# Schemat_easy_eda.net
KiCad netlist of a schematic drawn in EasyEDA
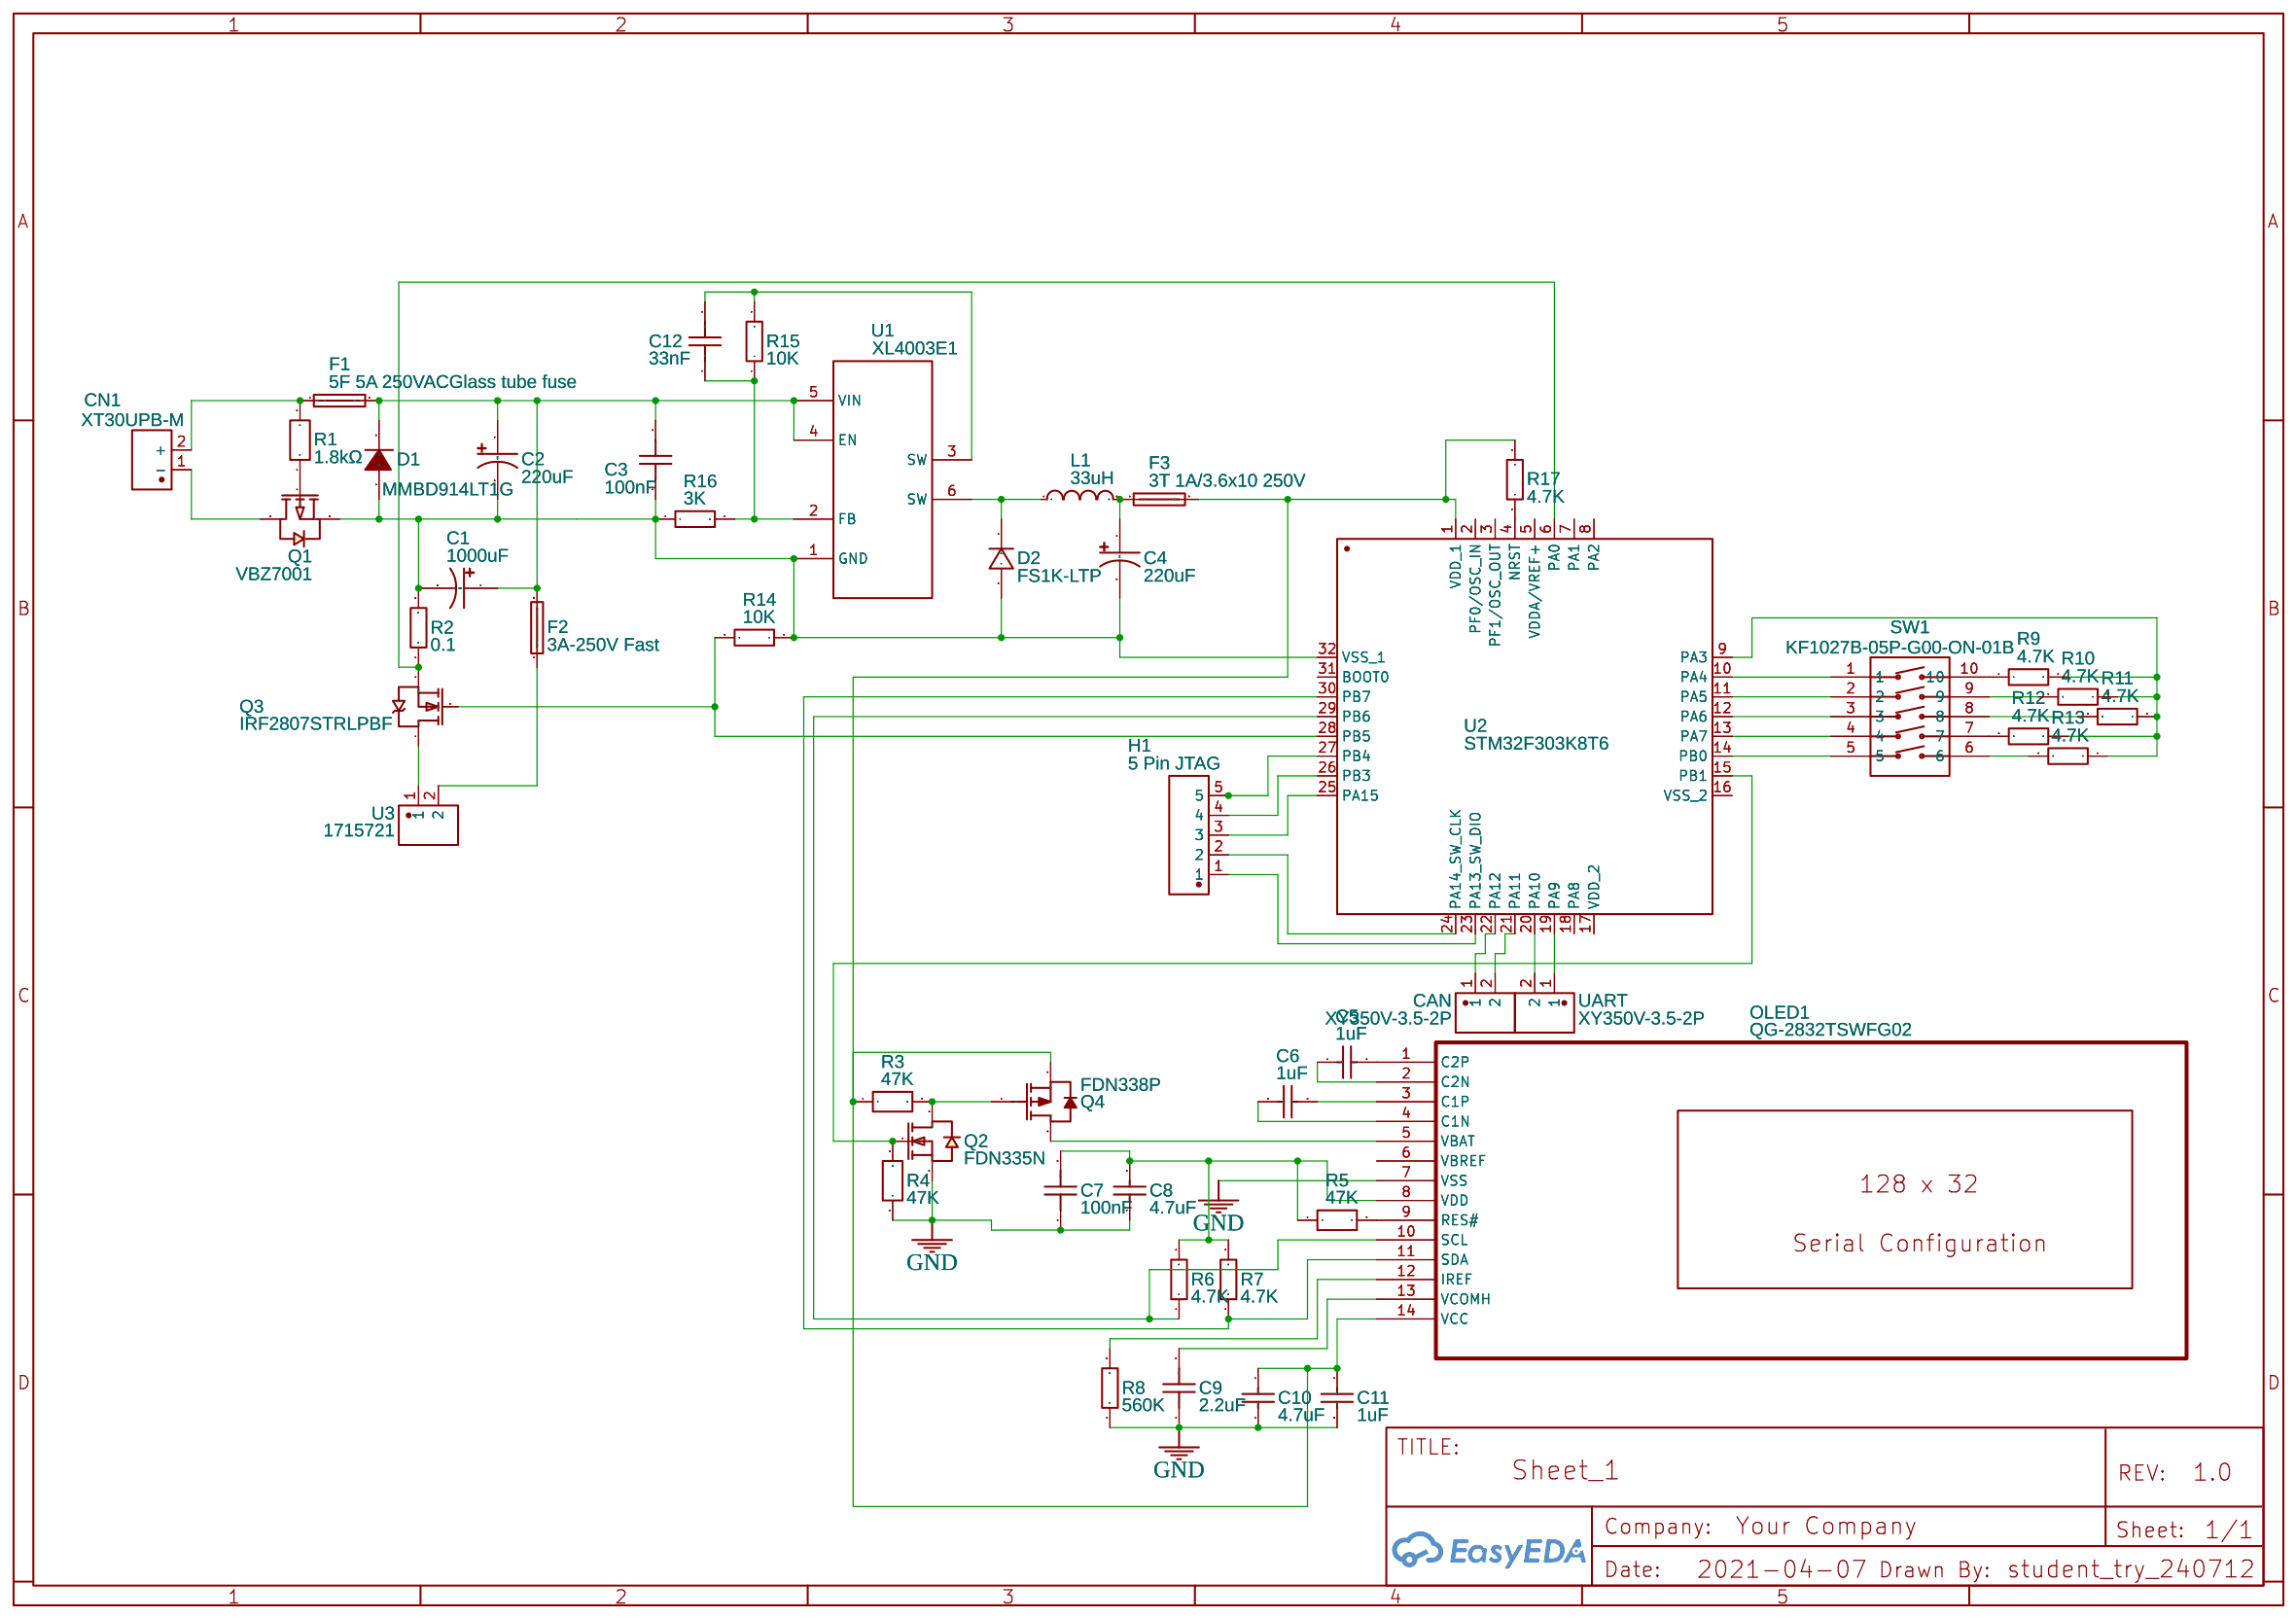
[diagram p0: schematic sheet]

(export (version "E")
  (design (tool "Eeschema 10.0.6"))
  (components
    (comp (ref "C1")
      (value "1000uF")
      (fields
        (field (name "BOM_Manufacturer Part") "LKME2301V102MF")
        (field (name "BOM_Supplier Part") "C442887")
      )
      (libsource (lib "") (part "LKME2301V102MF"))
    )
    (comp (ref "C2")
      (value "220uF")
      (fields
        (field (name "BOM_Manufacturer Part") "RVE1V221M1010")
        (field (name "BOM_Supplier Part") "C88670")
      )
      (libsource (lib "") (part "RVE1V221M1010"))
    )
    (comp (ref "C3")
      (value "100nF")
      (fields
        (field (name "BOM_Manufacturer Part") "CC1H104ZA1FD3F5P10MF")
        (field (name "BOM_Supplier Part") "C254089")
      )
      (libsource (lib "") (part "CC1H104ZA1FD3F5P10MF"))
    )
    (comp (ref "C4")
      (value "220uF")
      (fields
        (field (name "BOM_Manufacturer Part") "VE-221M0JTR-0605")
        (field (name "BOM_Supplier Part") "C134730")
      )
      (libsource (lib "") (part "VE-221M0JTR-0605"))
    )
    (comp (ref "C5")
      (value "1uF")
      (fields
        (field (name "BOM_Manufacturer Part") "CL10B105KA8NNNC")
        (field (name "BOM_Supplier Part") "C29936")
      )
      (libsource (lib "") (part "CL10B105KA8NNNC"))
    )
    (comp (ref "C6")
      (value "1uF")
      (fields
        (field (name "BOM_Manufacturer Part") "CL10B105KA8NNNC")
        (field (name "BOM_Supplier Part") "C29936")
      )
      (libsource (lib "") (part "CL10B105KA8NNNC"))
    )
    (comp (ref "C7")
      (value "100nF")
      (fields
        (field (name "BOM_Manufacturer Part") "GRM155F11C104ZA01D")
        (field (name "BOM_Supplier Part") "C85954")
      )
      (libsource (lib "") (part "GRM155F11C104ZA01D"))
    )
    (comp (ref "C8")
      (value "4.7uF")
      (fields
        (field (name "BOM_Manufacturer Part") "C2012X7R1A475KT000N")
        (field (name "BOM_Supplier Part") "C76639")
      )
      (libsource (lib "") (part "C2012X7R1A475KT000N"))
    )
    (comp (ref "C9")
      (value "2.2uF")
      (fields
        (field (name "BOM_Manufacturer Part") "GRM188R6YA225KA12D")
        (field (name "BOM_Supplier Part") "C86017")
      )
      (libsource (lib "") (part "GRM188R6YA225KA12D"))
    )
    (comp (ref "C10")
      (value "4.7uF")
      (fields
        (field (name "BOM_Manufacturer Part") "C2012X7R1A475KT000N")
        (field (name "BOM_Supplier Part") "C76639")
      )
      (libsource (lib "") (part "C2012X7R1A475KT000N"))
    )
    (comp (ref "C11")
      (value "1uF")
      (fields
        (field (name "BOM_Manufacturer Part") "CL10B105KA8NNNC")
        (field (name "BOM_Supplier Part") "C29936")
      )
      (libsource (lib "") (part "CL10B105KA8NNNC_1"))
    )
    (comp (ref "C12")
      (value "33nF")
      (fields
        (field (name "BOM_Manufacturer Part") "SMEC333J100M1")
        (field (name "BOM_Supplier Part") "C401102")
      )
      (libsource (lib "") (part "SMEC333J100M1"))
    )
    (comp (ref "CAN")
      (value "XY350V-3.5-2P")
      (fields (field (name "BOM_Supplier Part") "C784942"))
      (libsource (lib "") (part "XY350V-3.5-2P_1"))
    )
    (comp (ref "CN1")
      (value "XT30UPB-M")
      (fields (field (name "BOM_Supplier Part") "C428721"))
      (libsource (lib "") (part "XT30UPB-M"))
    )
    (comp (ref "D1")
      (value "MMBD914LT1G")
      (fields (field (name "BOM_Supplier Part") "C46523"))
      (libsource (lib "") (part "MMBD914LT1G"))
    )
    (comp (ref "D2")
      (value "FS1K-LTP")
      (fields (field (name "BOM_Supplier Part") "C725310"))
      (libsource (lib "") (part "FS1K-LTP"))
    )
    (comp (ref "F1")
      (value "5F 5A 250VACGlass tube fuse")
      (fields (field (name "BOM_Supplier Part") "C3120"))
      (libsource (lib "") (part "5F 5A 250VACGlass tube fuse"))
    )
    (comp (ref "F2")
      (value "3A-250V Fast")
      (fields
        (field (name "BOM_Manufacturer Part") "保险管3A-250V,带引脚 双帽")
        (field (name "BOM_Supplier Part") "C47403")
      )
      (libsource (lib "") (part "3A-250V"))
    )
    (comp (ref "F3")
      (value "3T 1A/3.6x10 250V")
      (fields (field (name "BOM_Supplier Part") "C40879"))
      (libsource (lib "") (part "3T 1A/3.6x10 250V"))
    )
    (comp (ref "H1")
      (value "5 Pin JTAG")
      (fields
        (field (name "BOM_Manufacturer Part") "210-81-05GB01")
        (field (name "BOM_Supplier Part") "C390676")
      )
      (libsource (lib "") (part "210-81-05GB01"))
    )
    (comp (ref "L1")
      (value "33uH")
      (fields
        (field (name "BOM_Manufacturer Part") "VLU0810-330K")
        (field (name "BOM_Supplier Part") "C72622")
      )
      (libsource (lib "") (part "VLU0810-330K"))
    )
    (comp (ref "OLED1")
      (value "QG-2832TSWFG02")
      (fields (field (name "BOM_Supplier Part") "C91219"))
      (libsource (lib "") (part "QG-2832TSWFG02"))
    )
    (comp (ref "Q1")
      (value "VBZ7001")
      (fields (field (name "BOM_Supplier Part") "C699531"))
      (libsource (lib "") (part "VBZ7001"))
    )
    (comp (ref "Q2")
      (value "FDN335N")
      (fields (field (name "BOM_Supplier Part") "C347512"))
      (libsource (lib "") (part "FDN335N"))
    )
    (comp (ref "Q3")
      (value "IRF2807STRLPBF")
      (fields (field (name "BOM_Supplier Part") "C97742"))
      (libsource (lib "") (part "IRF2807STRLPBF"))
    )
    (comp (ref "Q4")
      (value "FDN338P")
      (fields (field (name "BOM_Supplier Part") "C24855"))
      (libsource (lib "") (part "FDN338P"))
    )
    (comp (ref "R1")
      (value "1.8kΩ")
      (fields
        (field (name "BOM_Manufacturer Part") "CF1/4W-1.8KΩ±5%T52")
        (field (name "BOM_Supplier Part") "C714304")
      )
      (libsource (lib "") (part "CF1/4W-1.8KΩ±5%T52"))
    )
    (comp (ref "R2")
      (value "0.1")
      (fields
        (field (name "BOM_Manufacturer Part") "MRF6432(2512)LR100JTS")
        (field (name "BOM_Supplier Part") "C76282")
      )
      (libsource (lib "") (part "MRF6432(2512)LR100JTS"))
    )
    (comp (ref "R3")
      (value "47K")
      (fields
        (field (name "BOM_Manufacturer Part") "RN 1/4W 47K F T/B A1")
        (field (name "BOM_Supplier Part") "C410613")
      )
      (libsource (lib "") (part "RN 1/4W 47K F T/B A1"))
    )
    (comp (ref "R4")
      (value "47K")
      (fields
        (field (name "BOM_Manufacturer Part") "RN 1/4W 47K F T/B A1")
        (field (name "BOM_Supplier Part") "C410613")
      )
      (libsource (lib "") (part "RN 1/4W 47K F T/B A1_1"))
    )
    (comp (ref "R5")
      (value "47K")
      (fields
        (field (name "BOM_Manufacturer Part") "RN 1/4W 47K F T/B A1")
        (field (name "BOM_Supplier Part") "C410613")
      )
      (libsource (lib "") (part "RN 1/4W 47K F T/B A1"))
    )
    (comp (ref "R6")
      (value "4.7K")
      (fields
        (field (name "BOM_Manufacturer Part") "RM04JTN472")
        (field (name "BOM_Supplier Part") "C147813")
      )
      (libsource (lib "") (part "RM04JTN472"))
    )
    (comp (ref "R7")
      (value "4.7K")
      (fields
        (field (name "BOM_Manufacturer Part") "RM04JTN472")
        (field (name "BOM_Supplier Part") "C147813")
      )
      (libsource (lib "") (part "RM04JTN472"))
    )
    (comp (ref "R8")
      (value "560K")
      (fields
        (field (name "BOM_Manufacturer Part") "AECR0603F560KK9")
        (field (name "BOM_Supplier Part") "C352308")
      )
      (libsource (lib "") (part "AECR0603F560KK9"))
    )
    (comp (ref "R9")
      (value "4.7K")
      (fields
        (field (name "BOM_Manufacturer Part") "RM04JTN472")
        (field (name "BOM_Supplier Part") "C147813")
      )
      (libsource (lib "") (part "RM04JTN472_2"))
    )
    (comp (ref "R10")
      (value "4.7K")
      (fields
        (field (name "BOM_Manufacturer Part") "RM04JTN472")
        (field (name "BOM_Supplier Part") "C147813")
      )
      (libsource (lib "") (part "RM04JTN472_1"))
    )
    (comp (ref "R11")
      (value "4.7K")
      (fields
        (field (name "BOM_Manufacturer Part") "RM04JTN472")
        (field (name "BOM_Supplier Part") "C147813")
      )
      (libsource (lib "") (part "RM04JTN472_1"))
    )
    (comp (ref "R12")
      (value "4.7K")
      (fields
        (field (name "BOM_Manufacturer Part") "RM04JTN472")
        (field (name "BOM_Supplier Part") "C147813")
      )
      (libsource (lib "") (part "RM04JTN472_1"))
    )
    (comp (ref "R13")
      (value "4.7K")
      (fields
        (field (name "BOM_Manufacturer Part") "RM04JTN472")
        (field (name "BOM_Supplier Part") "C147813")
      )
      (libsource (lib "") (part "RM04JTN472_1"))
    )
    (comp (ref "R14")
      (value "10K")
      (fields
        (field (name "BOM_Manufacturer Part") "NQ02WGF1002TCE")
        (field (name "BOM_Supplier Part") "C270381")
      )
      (libsource (lib "") (part "NQ02WGF1002TCE"))
    )
    (comp (ref "R15")
      (value "10K")
      (fields
        (field (name "BOM_Manufacturer Part") "1210W3J0103T5E")
        (field (name "BOM_Supplier Part") "C25672")
      )
      (libsource (lib "") (part "1210W3J0103T5E"))
    )
    (comp (ref "R16")
      (value "3K")
      (fields
        (field (name "BOM_Manufacturer Part") "0603WAJ0302T5E")
        (field (name "BOM_Supplier Part") "C25597")
      )
      (libsource (lib "") (part "0603WAJ0302T5E"))
    )
    (comp (ref "R17")
      (value "4.7K")
      (fields
        (field (name "BOM_Manufacturer Part") "RM04JTN472")
        (field (name "BOM_Supplier Part") "C147813")
      )
      (libsource (lib "") (part "RM04JTN472"))
    )
    (comp (ref "SW1")
      (value "KF1027B-05P-G00-ON-01B")
      (fields (field (name "BOM_Supplier Part") "C976367"))
      (libsource (lib "") (part "KF1027B-05P-G00-ON-01B"))
    )
    (comp (ref "U1")
      (value "XL4003E1")
      (fields (field (name "BOM_Supplier Part") "C55888"))
      (libsource (lib "") (part "XL4003E1"))
    )
    (comp (ref "U2")
      (value "STM32F303K8T6")
      (fields (field (name "BOM_Supplier Part") "C118318"))
      (libsource (lib "") (part "STM32F303K8T6"))
    )
    (comp (ref "U3")
      (value "1715721")
      (fields (field (name "BOM_Supplier Part") "C480516"))
      (libsource (lib "") (part "1715721"))
    )
    (comp (ref "UART")
      (value "XY350V-3.5-2P")
      (fields (field (name "BOM_Supplier Part") "C784942"))
      (libsource (lib "") (part "XY350V-3.5-2P"))
    )
  )
  (nets
    (net (code "1") (name "GND") (class "Default")
      (node (ref "C10") (pin "1") (pinfunction "1_1") (pintype "input"))
      (node (ref "C11") (pin "1") (pinfunction "1_1") (pintype "input"))
      (node (ref "C7") (pin "1") (pinfunction "1_1") (pintype "unspecified"))
      (node (ref "C8") (pin "1") (pinfunction "1_1") (pintype "input"))
      (node (ref "C9") (pin "1") (pinfunction "1_1") (pintype "unspecified"))
      (node (ref "OLED1") (pin "7") (pinfunction "VSS_7") (pintype "passive"))
      (node (ref "Q2") (pin "2") (pinfunction "S_2") (pintype "unspecified"))
      (node (ref "R4") (pin "1") (pinfunction "1_1") (pintype "unspecified"))
      (node (ref "R8") (pin "1") (pinfunction "1_1") (pintype "unspecified"))
    )
    (net (code "2") (name "Net-(C4-Pad1)") (class "Default")
      (node (ref "C4") (pin "1") (pinfunction "1_1") (pintype "unspecified"))
      (node (ref "F3") (pin "1") (pinfunction "1_1") (pintype "unspecified"))
      (node (ref "L1") (pin "2") (pinfunction "2_2") (pintype "unspecified"))
    )
    (net (code "3") (name "Net-(C12-Pad2)") (class "Default")
      (node (ref "C12") (pin "2") (pinfunction "2_2") (pintype "unspecified"))
      (node (ref "R15") (pin "2") (pinfunction "2_2") (pintype "input"))
      (node (ref "U1") (pin "3") (pinfunction "SW_3") (pintype "unspecified"))
    )
    (net (code "4") (name "Net-(CN1-+)") (class "Default")
      (node (ref "CN1") (pin "2") (pinfunction "+_2") (pintype "unspecified"))
      (node (ref "F1") (pin "1") (pinfunction "1_1") (pintype "unspecified"))
      (node (ref "R1") (pin "2") (pinfunction "2_2") (pintype "unspecified"))
    )
    (net (code "5") (name "Net-(CN1--)") (class "Default")
      (node (ref "CN1") (pin "1") (pinfunction "-_1") (pintype "unspecified"))
      (node (ref "Q1") (pin "3") (pinfunction "D_3") (pintype "unspecified"))
    )
    (net (code "6") (name "Net-(D1-A)") (class "Default")
      (node (ref "C1") (pin "2") (pinfunction "2_2") (pintype "unspecified"))
      (node (ref "C2") (pin "2") (pinfunction "2_2") (pintype "unspecified"))
      (node (ref "C3") (pin "1") (pinfunction "1_1") (pintype "unspecified"))
      (node (ref "C4") (pin "2") (pinfunction "2_2") (pintype "unspecified"))
      (node (ref "D1") (pin "1") (pinfunction "A_1") (pintype "unspecified"))
      (node (ref "D2") (pin "2") (pinfunction "A_2") (pintype "unspecified"))
      (node (ref "Q1") (pin "2") (pinfunction "S_2") (pintype "unspecified"))
      (node (ref "R14") (pin "1") (pinfunction "1_1") (pintype "unspecified"))
      (node (ref "R16") (pin "1") (pinfunction "1_1") (pintype "input"))
      (node (ref "R2") (pin "2") (pinfunction "2_2") (pintype "input"))
      (node (ref "U1") (pin "1") (pinfunction "GND_1") (pintype "unspecified"))
      (node (ref "U2") (pin "32") (pinfunction "VSS_1_32") (pintype "unspecified"))
    )
    (net (code "7") (name "Net-(D1-K)") (class "Default")
      (node (ref "C1") (pin "1") (pinfunction "1_1") (pintype "unspecified"))
      (node (ref "C2") (pin "1") (pinfunction "1_1") (pintype "unspecified"))
      (node (ref "C3") (pin "2") (pinfunction "2_2") (pintype "unspecified"))
      (node (ref "D1") (pin "3") (pinfunction "K_3") (pintype "unspecified"))
      (node (ref "F1") (pin "2") (pinfunction "2_2") (pintype "unspecified"))
      (node (ref "F2") (pin "2") (pinfunction "2_2") (pintype "unspecified"))
      (node (ref "U1") (pin "4") (pinfunction "EN_4") (pintype "unspecified"))
      (node (ref "U1") (pin "5") (pinfunction "VIN_5") (pintype "unspecified"))
    )
    (net (code "8") (name "Net-(D2-C)") (class "Default")
      (node (ref "D2") (pin "1") (pinfunction "C_1") (pintype "unspecified"))
      (node (ref "L1") (pin "1") (pinfunction "1_1") (pintype "unspecified"))
      (node (ref "U1") (pin "6") (pinfunction "SW_6") (pintype "unspecified"))
    )
    (net (code "9") (name "Net-(F2-Pad1)") (class "Default")
      (node (ref "F2") (pin "1") (pinfunction "1_1") (pintype "unspecified"))
      (node (ref "U3") (pin "2") (pinfunction "2_2") (pintype "unspecified"))
    )
    (net (code "10") (name "Net-(OLED1-C1N)") (class "Default")
      (node (ref "C6") (pin "1") (pinfunction "1_1") (pintype "input"))
      (node (ref "OLED1") (pin "4") (pinfunction "C1N_4") (pintype "passive"))
    )
    (net (code "11") (name "Net-(OLED1-C1P)") (class "Default")
      (node (ref "C6") (pin "2") (pinfunction "2_2") (pintype "input"))
      (node (ref "OLED1") (pin "3") (pinfunction "C1P_3") (pintype "passive"))
    )
    (net (code "12") (name "Net-(OLED1-C2N)") (class "Default")
      (node (ref "C5") (pin "1") (pinfunction "1_1") (pintype "input"))
      (node (ref "OLED1") (pin "2") (pinfunction "C2N_2") (pintype "passive"))
    )
    (net (code "13") (name "Net-(OLED1-C2P)") (class "Default")
      (node (ref "C5") (pin "2") (pinfunction "2_2") (pintype "input"))
      (node (ref "OLED1") (pin "1") (pinfunction "C2P_1") (pintype "passive"))
    )
    (net (code "14") (name "Net-(OLED1-IREF)") (class "Default")
      (node (ref "OLED1") (pin "12") (pinfunction "IREF_12") (pintype "passive"))
      (node (ref "R8") (pin "2") (pinfunction "2_2") (pintype "unspecified"))
    )
    (net (code "15") (name "Net-(OLED1-RES#)") (class "Default")
      (node (ref "OLED1") (pin "9") (pinfunction "RES#_9") (pintype "passive"))
      (node (ref "R5") (pin "2") (pinfunction "2_2") (pintype "unspecified"))
    )
    (net (code "16") (name "Net-(OLED1-SCL)") (class "Default")
      (node (ref "OLED1") (pin "10") (pinfunction "SCL_10") (pintype "passive"))
      (node (ref "R6") (pin "1") (pinfunction "1_1") (pintype "unspecified"))
      (node (ref "U2") (pin "29") (pinfunction "PB6_29") (pintype "unspecified"))
    )
    (net (code "17") (name "Net-(OLED1-SDA)") (class "Default")
      (node (ref "OLED1") (pin "11") (pinfunction "SDA_11") (pintype "passive"))
      (node (ref "R7") (pin "1") (pinfunction "1_1") (pintype "unspecified"))
      (node (ref "U2") (pin "30") (pinfunction "PB7_30") (pintype "unspecified"))
    )
    (net (code "18") (name "Net-(OLED1-VBAT)") (class "Default")
      (node (ref "OLED1") (pin "5") (pinfunction "VBAT_5") (pintype "passive"))
      (node (ref "Q4") (pin "3") (pinfunction "D_3") (pintype "unspecified"))
    )
    (net (code "19") (name "Net-(OLED1-VCC)") (class "Default")
      (node (ref "C10") (pin "2") (pinfunction "2_2") (pintype "input"))
      (node (ref "C11") (pin "2") (pinfunction "2_2") (pintype "input"))
      (node (ref "F3") (pin "2") (pinfunction "2_2") (pintype "unspecified"))
      (node (ref "OLED1") (pin "14") (pinfunction "VCC_14") (pintype "passive"))
      (node (ref "Q4") (pin "2") (pinfunction "S_2") (pintype "unspecified"))
      (node (ref "R17") (pin "2") (pinfunction "2_2") (pintype "unspecified"))
      (node (ref "R3") (pin "1") (pinfunction "1_1") (pintype "unspecified"))
      (node (ref "U2") (pin "1") (pinfunction "VDD_1_1") (pintype "unspecified"))
    )
    (net (code "20") (name "Net-(OLED1-VCOMH)") (class "Default")
      (node (ref "C9") (pin "2") (pinfunction "2_2") (pintype "unspecified"))
      (node (ref "OLED1") (pin "13") (pinfunction "VCOMH_13") (pintype "passive"))
    )
    (net (code "21") (name "Net-(OLED1-VDD)") (class "Default")
      (node (ref "C7") (pin "2") (pinfunction "2_2") (pintype "unspecified"))
      (node (ref "C8") (pin "2") (pinfunction "2_2") (pintype "input"))
      (node (ref "OLED1") (pin "8") (pinfunction "VDD_8") (pintype "passive"))
      (node (ref "R5") (pin "1") (pinfunction "1_1") (pintype "unspecified"))
      (node (ref "R6") (pin "2") (pinfunction "2_2") (pintype "unspecified"))
      (node (ref "R7") (pin "2") (pinfunction "2_2") (pintype "unspecified"))
    )
    (net (code "22") (name "Net-(Q1-G)") (class "Default")
      (node (ref "Q1") (pin "1") (pinfunction "G_1") (pintype "unspecified"))
      (node (ref "R1") (pin "1") (pinfunction "1_1") (pintype "unspecified"))
    )
    (net (code "23") (name "Net-(Q2-D)") (class "Default")
      (node (ref "Q2") (pin "3") (pinfunction "D_3") (pintype "unspecified"))
      (node (ref "Q4") (pin "1") (pinfunction "G_1") (pintype "unspecified"))
      (node (ref "R3") (pin "2") (pinfunction "2_2") (pintype "unspecified"))
    )
    (net (code "24") (name "Net-(Q2-G)") (class "Default")
      (node (ref "Q2") (pin "1") (pinfunction "G_1") (pintype "unspecified"))
      (node (ref "R4") (pin "2") (pinfunction "2_2") (pintype "unspecified"))
      (node (ref "U2") (pin "15") (pinfunction "PB1_15") (pintype "unspecified"))
    )
    (net (code "25") (name "Net-(Q3-D)") (class "Default")
      (node (ref "Q3") (pin "4") (pinfunction "D_4") (pintype "unspecified"))
      (node (ref "U3") (pin "1") (pinfunction "1_1") (pintype "unspecified"))
    )
    (net (code "26") (name "Net-(Q3-G)") (class "Default")
      (node (ref "Q3") (pin "1") (pinfunction "G_1") (pintype "unspecified"))
      (node (ref "R14") (pin "2") (pinfunction "2_2") (pintype "unspecified"))
      (node (ref "U2") (pin "28") (pinfunction "PB5_28") (pintype "unspecified"))
    )
    (net (code "27") (name "Net-(Q3-S)") (class "Default")
      (node (ref "Q3") (pin "3") (pinfunction "S_3") (pintype "unspecified"))
      (node (ref "R2") (pin "1") (pinfunction "1_1") (pintype "input"))
      (node (ref "U2") (pin "6") (pinfunction "PA0_6") (pintype "unspecified"))
    )
    (net (code "28") (name "Net-(R9-Pad1)") (class "Default")
      (node (ref "R9") (pin "1") (pinfunction "1_1") (pintype "unspecified"))
      (node (ref "SW1") (pin "10") (pinfunction "10_10") (pintype "unspecified"))
    )
    (net (code "29") (name "Net-(R10-Pad2)") (class "Default")
      (node (ref "R10") (pin "2") (pinfunction "2_2") (pintype "unspecified"))
      (node (ref "SW1") (pin "9") (pinfunction "9_9") (pintype "unspecified"))
    )
    (net (code "30") (name "Net-(R11-Pad2)") (class "Default")
      (node (ref "R11") (pin "2") (pinfunction "2_2") (pintype "unspecified"))
      (node (ref "SW1") (pin "8") (pinfunction "8_8") (pintype "unspecified"))
    )
    (net (code "31") (name "Net-(R12-Pad2)") (class "Default")
      (node (ref "R12") (pin "2") (pinfunction "2_2") (pintype "unspecified"))
      (node (ref "SW1") (pin "7") (pinfunction "7_7") (pintype "unspecified"))
    )
    (net (code "32") (name "Net-(R13-Pad2)") (class "Default")
      (node (ref "R13") (pin "2") (pinfunction "2_2") (pintype "unspecified"))
      (node (ref "SW1") (pin "6") (pinfunction "6_6") (pintype "unspecified"))
    )
    (net (code "33") (name "Net-(U1-FB)") (class "Default")
      (node (ref "C12") (pin "1") (pinfunction "1_1") (pintype "unspecified"))
      (node (ref "R15") (pin "1") (pinfunction "1_1") (pintype "input"))
      (node (ref "R16") (pin "2") (pinfunction "2_2") (pintype "input"))
      (node (ref "U1") (pin "2") (pinfunction "FB_2") (pintype "unspecified"))
    )
    (net (code "34") (name "Net-(U2-NRST)") (class "Default")
      (node (ref "R17") (pin "1") (pinfunction "1_1") (pintype "unspecified"))
      (node (ref "U2") (pin "4") (pinfunction "NRST_4") (pintype "unspecified"))
    )
    (net (code "35") (name "Net-(U2-PA3)") (class "Default")
      (node (ref "R10") (pin "1") (pinfunction "1_1") (pintype "unspecified"))
      (node (ref "R11") (pin "1") (pinfunction "1_1") (pintype "unspecified"))
      (node (ref "R12") (pin "1") (pinfunction "1_1") (pintype "unspecified"))
      (node (ref "R13") (pin "1") (pinfunction "1_1") (pintype "unspecified"))
      (node (ref "R9") (pin "2") (pinfunction "2_2") (pintype "unspecified"))
      (node (ref "U2") (pin "9") (pinfunction "PA3_9") (pintype "unspecified"))
    )
    (net (code "36") (name "Net-(U2-PA4)") (class "Default")
      (node (ref "SW1") (pin "1") (pinfunction "1_1") (pintype "unspecified"))
      (node (ref "U2") (pin "10") (pinfunction "PA4_10") (pintype "unspecified"))
    )
    (net (code "37") (name "Net-(U2-PA5)") (class "Default")
      (node (ref "SW1") (pin "2") (pinfunction "2_2") (pintype "unspecified"))
      (node (ref "U2") (pin "11") (pinfunction "PA5_11") (pintype "unspecified"))
    )
    (net (code "38") (name "Net-(U2-PA6)") (class "Default")
      (node (ref "SW1") (pin "3") (pinfunction "3_3") (pintype "unspecified"))
      (node (ref "U2") (pin "12") (pinfunction "PA6_12") (pintype "unspecified"))
    )
    (net (code "39") (name "Net-(U2-PA7)") (class "Default")
      (node (ref "SW1") (pin "4") (pinfunction "4_4") (pintype "unspecified"))
      (node (ref "U2") (pin "13") (pinfunction "PA7_13") (pintype "unspecified"))
    )
    (net (code "40") (name "Net-(U2-PA9)") (class "Default")
      (node (ref "U2") (pin "19") (pinfunction "PA9_19") (pintype "unspecified"))
      (node (ref "UART") (pin "1") (pinfunction "1_1") (pintype "unspecified"))
    )
    (net (code "41") (name "Net-(U2-PA10)") (class "Default")
      (node (ref "U2") (pin "20") (pinfunction "PA10_20") (pintype "unspecified"))
      (node (ref "UART") (pin "2") (pinfunction "2_2") (pintype "unspecified"))
    )
    (net (code "42") (name "Net-(U2-PA11)") (class "Default")
      (node (ref "CAN") (pin "2") (pinfunction "2_2") (pintype "unspecified"))
      (node (ref "U2") (pin "21") (pinfunction "PA11_21") (pintype "unspecified"))
    )
    (net (code "43") (name "Net-(U2-PA12)") (class "Default")
      (node (ref "CAN") (pin "1") (pinfunction "1_1") (pintype "unspecified"))
      (node (ref "U2") (pin "22") (pinfunction "PA12_22") (pintype "unspecified"))
    )
    (net (code "44") (name "Net-(U2-PA13_SW_DIO)") (class "Default")
      (node (ref "H1") (pin "1") (pinfunction "1_1") (pintype "unspecified"))
      (node (ref "U2") (pin "23") (pinfunction "PA13_SW_DIO_23") (pintype "unspecified"))
    )
    (net (code "45") (name "Net-(U2-PA14_SW_CLK)") (class "Default")
      (node (ref "H1") (pin "2") (pinfunction "2_2") (pintype "unspecified"))
      (node (ref "U2") (pin "24") (pinfunction "PA14_SW_CLK_24") (pintype "unspecified"))
    )
    (net (code "46") (name "Net-(U2-PA15)") (class "Default")
      (node (ref "H1") (pin "3") (pinfunction "3_3") (pintype "unspecified"))
      (node (ref "U2") (pin "25") (pinfunction "PA15_25") (pintype "unspecified"))
    )
    (net (code "47") (name "Net-(U2-PB0)") (class "Default")
      (node (ref "SW1") (pin "5") (pinfunction "5_5") (pintype "unspecified"))
      (node (ref "U2") (pin "14") (pinfunction "PB0_14") (pintype "unspecified"))
    )
    (net (code "48") (name "Net-(U2-PB3)") (class "Default")
      (node (ref "H1") (pin "4") (pinfunction "4_4") (pintype "unspecified"))
      (node (ref "U2") (pin "26") (pinfunction "PB3_26") (pintype "unspecified"))
    )
    (net (code "49") (name "Net-(U2-PB4)") (class "Default")
      (node (ref "H1") (pin "5") (pinfunction "5_5") (pintype "unspecified"))
      (node (ref "U2") (pin "27") (pinfunction "PB4_27") (pintype "unspecified"))
    )
    (net (code "50") (name "unconnected-(OLED1-VBREF-Pad6)") (class "Default")
      (node (ref "OLED1") (pin "6") (pinfunction "VBREF_6") (pintype "passive"))
    )
    (net (code "51") (name "unconnected-(U2-BOOT0-Pad31)") (class "Default")
      (node (ref "U2") (pin "31") (pinfunction "BOOT0_31") (pintype "unspecified"))
    )
    (net (code "52") (name "unconnected-(U2-PA1-Pad7)") (class "Default")
      (node (ref "U2") (pin "7") (pinfunction "PA1_7") (pintype "unspecified"))
    )
    (net (code "53") (name "unconnected-(U2-PA2-Pad8)") (class "Default")
      (node (ref "U2") (pin "8") (pinfunction "PA2_8") (pintype "unspecified"))
    )
    (net (code "54") (name "unconnected-(U2-PA8-Pad18)") (class "Default")
      (node (ref "U2") (pin "18") (pinfunction "PA8_18") (pintype "unspecified"))
    )
    (net (code "55") (name "unconnected-(U2-PF0{slash}OSC_IN-Pad2)") (class "Default")
      (node (ref "U2") (pin "2") (pinfunction "PF0/OSC_IN_2") (pintype "unspecified"))
    )
    (net (code "56") (name "unconnected-(U2-PF1{slash}OSC_OUT-Pad3)") (class "Default")
      (node (ref "U2") (pin "3") (pinfunction "PF1/OSC_OUT_3") (pintype "unspecified"))
    )
    (net (code "57") (name "unconnected-(U2-VDDA{slash}VREF+-Pad5)") (class "Default")
      (node (ref "U2") (pin "5") (pinfunction "VDDA/VREF+_5") (pintype "unspecified"))
    )
    (net (code "58") (name "unconnected-(U2-VDD_2-Pad17)") (class "Default")
      (node (ref "U2") (pin "17") (pinfunction "VDD_2_17") (pintype "unspecified"))
    )
    (net (code "59") (name "unconnected-(U2-VSS_2-Pad16)") (class "Default")
      (node (ref "U2") (pin "16") (pinfunction "VSS_2_16") (pintype "unspecified"))
    )
  )
)
